# led_supply.net
KiCad netlist of a schematic drawn in Altium Designer
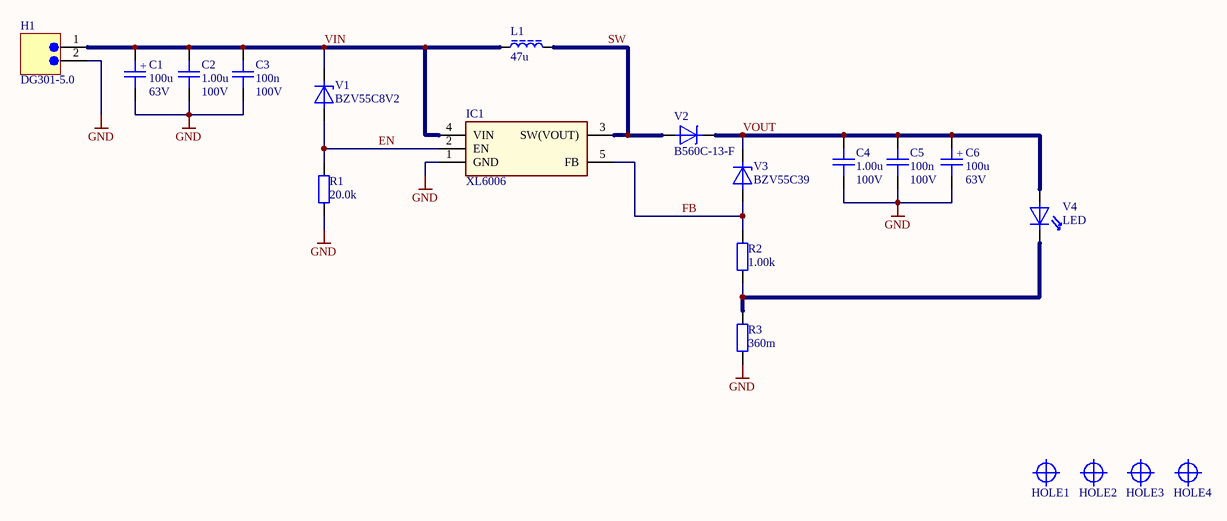
[diagram p0: led_supply.SchDoc]

(export (version "E")
  (design (tool "Eeschema 10.0.6"))
  (components
    (comp (ref "C1")
      (value "100u")
      (footprint "sm_cap_elyt10m")
      (description "CAP ELYT 47u 50V low ESR 10mm")
      (fields
        (field (name "VOLTAGE") "63V")
        (field (name "PART NUMBER") "CAP_000411")
        (field (name "TOLERANCE") "20%")
        (field (name "PUBLISHER") "Libor Polacek")
        (field (name "DESIGNER") "Jiri  Cengery")
      )
      (libsource (lib "Lib_Components_SQL") (part "cap_el"))
    )
    (comp (ref "C2")
      (value "1.00u")
      (footprint "sm_cap_1206")
      (description "CAP CER 1.00u 100V X7R 10% 1206")
      (fields
        (field (name "VOLTAGE") "100V")
        (field (name "PART NUMBER") "CAP_000356")
        (field (name "TOLERANCE") "10%")
        (field (name "PUBLISHER") "Libor Polacek")
        (field (name "DESIGNER") "MaJa")
      )
      (libsource (lib "Lib_Components_SQL") (part "cap_volt"))
    )
    (comp (ref "C3")
      (value "100n")
      (footprint "sm_cap_1206")
      (description "CAP CER 100n 100V X7R 10% 1206")
      (fields
        (field (name "VOLTAGE") "100V")
        (field (name "PART NUMBER") "CAP_000351")
        (field (name "TOLERANCE") "10%")
        (field (name "PUBLISHER") "Libor Polacek")
        (field (name "DESIGNER") "MaJa")
      )
      (libsource (lib "Lib_Components_SQL") (part "cap_volt"))
    )
    (comp (ref "C4")
      (value "1.00u")
      (footprint "sm_cap_1206")
      (description "CAP CER 1.00u 100V X7R 10% 1206")
      (fields
        (field (name "VOLTAGE") "100V")
        (field (name "PART NUMBER") "CAP_000356")
        (field (name "TOLERANCE") "10%")
        (field (name "PUBLISHER") "Libor Polacek")
        (field (name "DESIGNER") "MaJa")
      )
      (libsource (lib "Lib_Components_SQL") (part "cap_volt"))
    )
    (comp (ref "C5")
      (value "100n")
      (footprint "sm_cap_1206")
      (description "CAP CER 100n 100V X7R 10% 1206")
      (fields
        (field (name "VOLTAGE") "100V")
        (field (name "PART NUMBER") "CAP_000351")
        (field (name "TOLERANCE") "10%")
        (field (name "PUBLISHER") "Libor Polacek")
        (field (name "DESIGNER") "MaJa")
      )
      (libsource (lib "Lib_Components_SQL") (part "cap_volt"))
    )
    (comp (ref "C6")
      (value "100u")
      (footprint "sm_cap_elyt10m")
      (description "CAP ELYT 47u 50V low ESR 10mm")
      (fields
        (field (name "VOLTAGE") "63V")
        (field (name "PART NUMBER") "CAP_000411")
        (field (name "TOLERANCE") "20%")
        (field (name "PUBLISHER") "Libor Polacek")
        (field (name "DESIGNER") "Jiri  Cengery")
      )
      (libsource (lib "Lib_Components_SQL") (part "cap_el"))
    )
    (comp (ref "H1")
      (value "DG301-5.0")
      (footprint "TH_CON_2PIN_PIT197")
      (description "CON 2pin power 197mill")
      (fields
        (field (name "PART NUMBER") "CON_000079")
        (field (name "MANUF PART NUMBER") "DG301-5.0-02P-12")
        (field (name "PUBLISHER") "Turjanica")
        (field (name "DESIGNER") "Tomáš Košan")
      )
      (libsource (lib "Lib_Components_SQL") (part "Header 2"))
    )
    (comp (ref "HOLE1")
      (value "HOLE_30")
      (footprint "th_mch_hole30m")
      (description "MCH test hole 3mm no pad")
      (fields
        (field (name "PART NUMBER") "MCH_000055")
        (field (name "MANUF PART NUMBER") "x")
        (field (name "PUBLISHER") "Jiri Svarny")
        (field (name "DESIGNER") "Jiri Cengery")
      )
      (libsource (lib "Lib_Components_SQL") (part "Hole_bare"))
    )
    (comp (ref "HOLE2")
      (value "HOLE_30")
      (footprint "th_mch_hole30m")
      (description "MCH test hole 3mm no pad")
      (fields
        (field (name "PART NUMBER") "MCH_000055")
        (field (name "MANUF PART NUMBER") "x")
        (field (name "PUBLISHER") "Jiri Svarny")
        (field (name "DESIGNER") "Jiri Cengery")
      )
      (libsource (lib "Lib_Components_SQL") (part "Hole_bare"))
    )
    (comp (ref "HOLE3")
      (value "HOLE_30")
      (footprint "th_mch_hole30m")
      (description "MCH test hole 3mm no pad")
      (fields
        (field (name "PART NUMBER") "MCH_000055")
        (field (name "MANUF PART NUMBER") "x")
        (field (name "PUBLISHER") "Jiri Svarny")
        (field (name "DESIGNER") "Jiri Cengery")
      )
      (libsource (lib "Lib_Components_SQL") (part "Hole_bare"))
    )
    (comp (ref "HOLE4")
      (value "HOLE_30")
      (footprint "th_mch_hole30m")
      (description "MCH test hole 3mm no pad")
      (fields
        (field (name "PART NUMBER") "MCH_000055")
        (field (name "MANUF PART NUMBER") "x")
        (field (name "PUBLISHER") "Jiri Svarny")
        (field (name "DESIGNER") "Jiri Cengery")
      )
      (libsource (lib "Lib_Components_SQL") (part "Hole_bare"))
    )
    (comp (ref "IC1")
      (value "XL6006")
      (footprint "XL6006")
      (description "180KHz 60V 5A Switching Current Boost LED Constant Current Driver")
      (libsource (lib "XL6006") (part "XL6006"))
    )
    (comp (ref "L1")
      (value "47u")
      (footprint "sm_ind_SRP1270")
      (description "IND 47u 5A 13.7x13.7mm ferrite")
      (fields
        (field (name "PART NUMBER") "IND_000080")
        (field (name "TOLERANCE") "20%")
        (field (name "PUBLISHER") "Libor Polacek")
        (field (name "DESIGNER") "Jiri Svarny")
      )
      (libsource (lib "Lib_Components_SQL") (part "ind_ferite"))
    )
    (comp (ref "R1")
      (value "20.0k")
      (footprint "sm_res_0805")
      (description "RES 0805 20.0k 1% 100ppm SMD thick film")
      (fields
        (field (name "PART NUMBER") "RES_000274")
        (field (name "TOLERANCE") "1%")
        (field (name "PUBLISHER") "Libor Polacek")
        (field (name "DESIGNER") "Kamil Kosturik")
      )
      (libsource (lib "Lib_Components_SQL") (part "res"))
    )
    (comp (ref "R2")
      (value "1.00k")
      (footprint "sm_res_0805")
      (description "RES 0805 1.00k 1% 100ppm SMD thick film")
      (fields
        (field (name "PART NUMBER") "RES_000243")
        (field (name "TOLERANCE") "1%")
        (field (name "PUBLISHER") "Libor Polacek")
        (field (name "DESIGNER") "Tomáš Košan")
      )
      (libsource (lib "Lib_Components_SQL") (part "res"))
    )
    (comp (ref "R3")
      (value "360m")
      (footprint "SM_RES_2512")
      (description "RES 2512 0.0R 1.5W SMD thick film")
      (fields
        (field (name "PART NUMBER") "RES_000543")
        (field (name "TOLERANCE") "1%")
        (field (name "PUBLISHER") "Libor Polacek")
        (field (name "DESIGNER") "Jiri  Cengery")
      )
      (libsource (lib "Lib_Components_SQL") (part "res"))
    )
    (comp (ref "V1")
      (value "BZV55C8V2")
      (footprint "sm_dio_minimelf_d59_l140")
      (description "DIO Diode zener 8V2; 500mW; miniMELF")
      (fields
        (field (name "PART NUMBER") "DIO_000033")
        (field (name "VOLTAGE") "8.2V")
        (field (name "PUBLISHER") "Libor Polacek")
        (field (name "DESIGNER") "Jiri Cengery")
      )
      (libsource (lib "Lib_Components_SQL") (part "Diode_zener"))
    )
    (comp (ref "V2")
      (value "B560C-13-F")
      (footprint "sm_dio_smc")
      (description "DIO Schottky 40V 5A SMC")
      (fields
        (field (name "PART NUMBER") "DIO_000095")
        (field (name "VOLTAGE") "40V")
        (field (name "PUBLISHER") "Libor Polacek")
        (field (name "DESIGNER") "Jiri  Cengery")
      )
      (libsource (lib "Lib_Components_SQL") (part "Diode_schottky"))
    )
    (comp (ref "V3")
      (value "BZV55C39")
      (footprint "sm_dio_minimelf_d59_l140")
      (description "DIO Diode zener 8V2; 500mW; miniMELF")
      (fields
        (field (name "PART NUMBER") "DIO_000033")
        (field (name "VOLTAGE") "8.2V")
        (field (name "PUBLISHER") "Libor Polacek")
        (field (name "DESIGNER") "Jiri Cengery")
      )
      (libsource (lib "Lib_Components_SQL") (part "Diode_zener"))
    )
    (comp (ref "V4")
      (value "LED")
      (footprint "PWR_LED")
      (description "Power LED 20 - 100W (40x42mm))")
      (libsource (lib "PWR_LED") (part "LED"))
    )
  )
  (nets
    (net (code "1") (name "/EN") (class "Default")
      (node (ref "IC1") (pin "2") (pinfunction "EN_2") (pintype "passive"))
      (node (ref "R1") (pin "2") (pinfunction "2_2") (pintype "passive"))
      (node (ref "V1") (pin "1") (pinfunction "A_1") (pintype "passive"))
    )
    (net (code "2") (name "/FB") (class "Default")
      (node (ref "IC1") (pin "5") (pinfunction "FB_5") (pintype "passive"))
      (node (ref "R2") (pin "2") (pinfunction "2_2") (pintype "passive"))
      (node (ref "V3") (pin "1") (pinfunction "A_1") (pintype "passive"))
    )
    (net (code "3") (name "/SW") (class "Default")
      (node (ref "IC1") (pin "3") (pinfunction "SW(VOUT)_3") (pintype "passive"))
      (node (ref "L1") (pin "2") (pinfunction "2_2") (pintype "passive"))
      (node (ref "V2") (pin "1") (pinfunction "A_1") (pintype "passive"))
    )
    (net (code "4") (name "/VIN") (class "Default")
      (node (ref "C1") (pin "1") (pinfunction "1_1") (pintype "passive"))
      (node (ref "C2") (pin "2") (pinfunction "2_2") (pintype "passive"))
      (node (ref "C3") (pin "2") (pinfunction "2_2") (pintype "passive"))
      (node (ref "H1") (pin "1") (pinfunction "1_1") (pintype "passive"))
      (node (ref "IC1") (pin "4") (pinfunction "VIN_4") (pintype "passive"))
      (node (ref "L1") (pin "1") (pinfunction "1_1") (pintype "passive"))
      (node (ref "V1") (pin "2") (pinfunction "C_2") (pintype "passive"))
    )
    (net (code "5") (name "/VOUT") (class "Default")
      (node (ref "C4") (pin "2") (pinfunction "2_2") (pintype "passive"))
      (node (ref "C5") (pin "2") (pinfunction "2_2") (pintype "passive"))
      (node (ref "C6") (pin "1") (pinfunction "1_1") (pintype "passive"))
      (node (ref "V2") (pin "2") (pinfunction "C_2") (pintype "passive"))
      (node (ref "V3") (pin "2") (pinfunction "C_2") (pintype "passive"))
      (node (ref "V4") (pin "1") (pinfunction "+_1") (pintype "passive"))
    )
    (net (code "6") (name "GND") (class "Default")
      (node (ref "C1") (pin "2") (pinfunction "2_2") (pintype "passive"))
      (node (ref "C2") (pin "1") (pinfunction "1_1") (pintype "passive"))
      (node (ref "C3") (pin "1") (pinfunction "1_1") (pintype "passive"))
      (node (ref "C4") (pin "1") (pinfunction "1_1") (pintype "passive"))
      (node (ref "C5") (pin "1") (pinfunction "1_1") (pintype "passive"))
      (node (ref "C6") (pin "2") (pinfunction "2_2") (pintype "passive"))
      (node (ref "H1") (pin "2") (pinfunction "2_2") (pintype "passive"))
      (node (ref "IC1") (pin "1") (pinfunction "GND_1") (pintype "passive"))
      (node (ref "R1") (pin "1") (pinfunction "1_1") (pintype "passive"))
      (node (ref "R3") (pin "1") (pinfunction "1_1") (pintype "passive"))
    )
    (net (code "7") (name "Net-(V4--)") (class "Default")
      (node (ref "R2") (pin "1") (pinfunction "1_1") (pintype "passive"))
      (node (ref "R3") (pin "2") (pinfunction "2_2") (pintype "passive"))
      (node (ref "V4") (pin "2") (pinfunction "-_2") (pintype "passive"))
    )
  )
)
